# picr22-team-snax-mainboard.net
KiCad netlist of a schematic drawn in Altium Designer
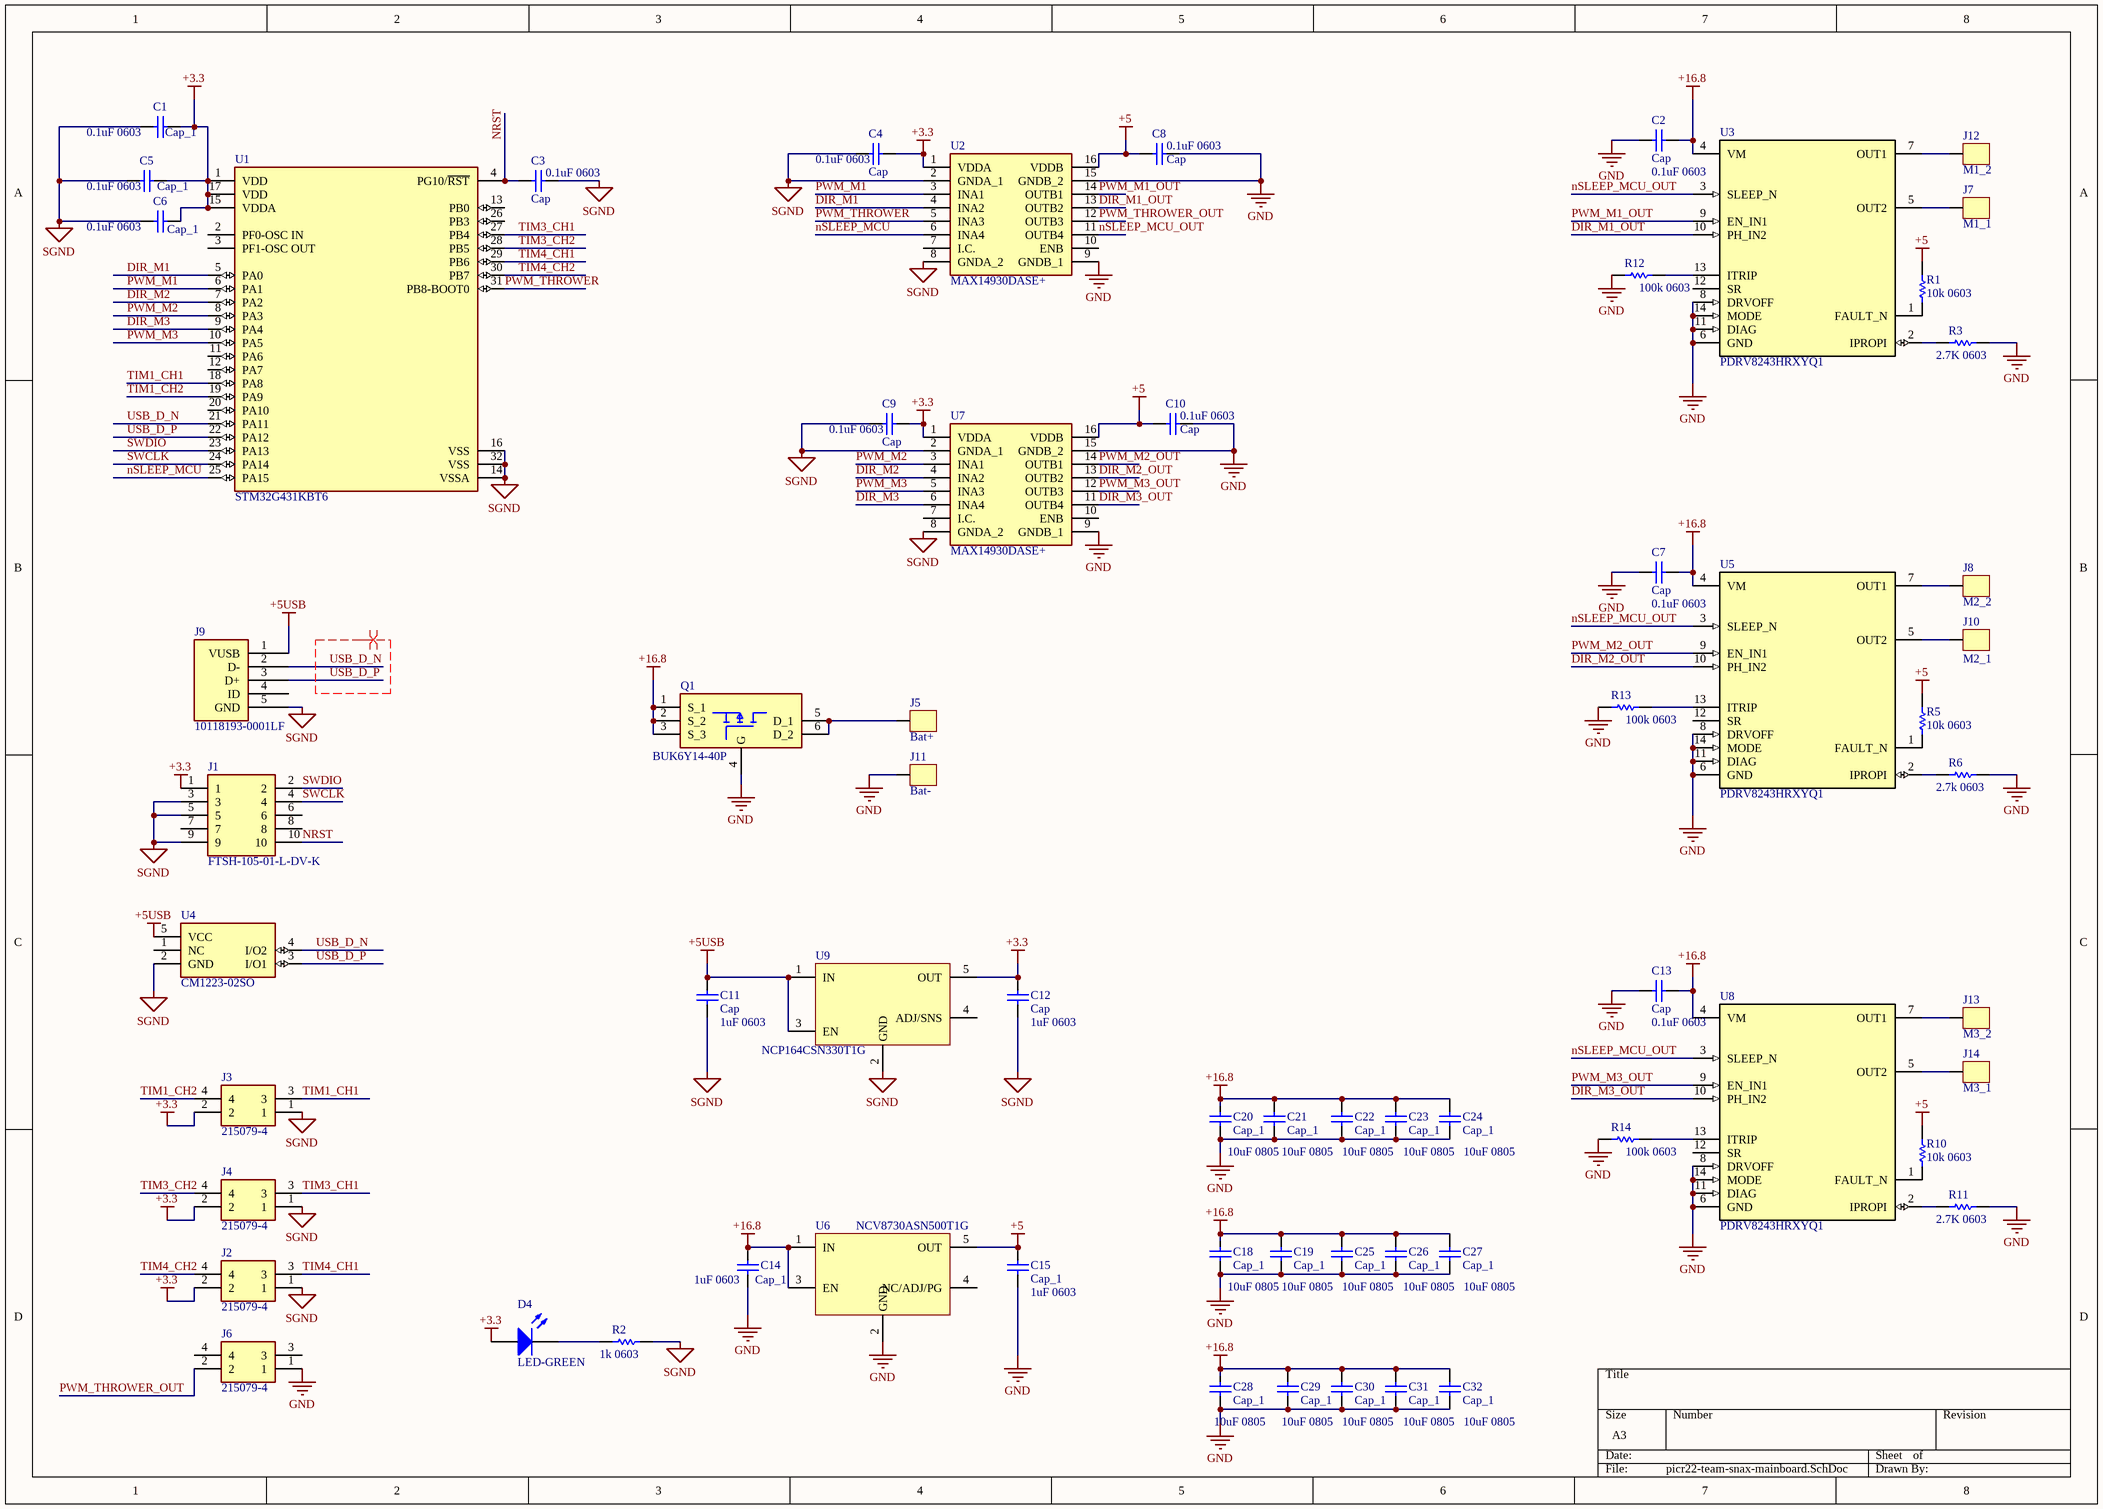
[diagram p0: picr22-team-snax-mainboard.SchDoc]

(export (version "E")
  (design (tool "Eeschema 10.0.6"))
  (components
    (comp (ref "C1")
      (value "Cap_1")
      (footprint "Cap_0603")
      (description "Capacitor")
      (fields (field (name "ALTIUM_VALUE") "0.1uF 0603") (field (name "PUBLISHER") "Altium Limited"))
      (libsource (lib "") (part "Cap_1"))
    )
    (comp (ref "C2")
      (value "Cap")
      (footprint "Cap_0603")
      (description "Capacitor")
      (fields (field (name "ALTIUM_VALUE") "0.1uF 0603") (field (name "PUBLISHER") "Altium Limited"))
      (libsource (lib "MotorDriver") (part "Cap"))
    )
    (comp (ref "C3")
      (value "Cap")
      (footprint "Cap_0603")
      (description "Capacitor")
      (fields (field (name "ALTIUM_VALUE") "0.1uF 0603") (field (name "PUBLISHER") "Altium Limited"))
      (libsource (lib "MotorDriver") (part "Cap"))
    )
    (comp (ref "C4")
      (value "Cap")
      (footprint "Cap_0603")
      (description "Capacitor")
      (fields (field (name "ALTIUM_VALUE") "0.1uF 0603") (field (name "PUBLISHER") "Altium Limited"))
      (libsource (lib "MotorDriver") (part "Cap"))
    )
    (comp (ref "C5")
      (value "Cap_1")
      (footprint "Cap_0603")
      (description "Capacitor")
      (fields (field (name "ALTIUM_VALUE") "0.1uF 0603") (field (name "PUBLISHER") "Altium Limited"))
      (libsource (lib "") (part "Cap_1"))
    )
    (comp (ref "C6")
      (value "Cap_1")
      (footprint "Cap_0603")
      (description "Capacitor")
      (fields (field (name "ALTIUM_VALUE") "0.1uF 0603") (field (name "PUBLISHER") "Altium Limited"))
      (libsource (lib "") (part "Cap_1"))
    )
    (comp (ref "C7")
      (value "Cap")
      (footprint "Cap_0603")
      (description "Capacitor")
      (fields (field (name "ALTIUM_VALUE") "0.1uF 0603") (field (name "PUBLISHER") "Altium Limited"))
      (libsource (lib "MotorDriver") (part "Cap"))
    )
    (comp (ref "C8")
      (value "Cap")
      (footprint "Cap_0603")
      (description "Capacitor")
      (fields (field (name "ALTIUM_VALUE") "0.1uF 0603") (field (name "PUBLISHER") "Altium Limited"))
      (libsource (lib "MotorDriver") (part "Cap"))
    )
    (comp (ref "C9")
      (value "Cap")
      (footprint "Cap_0603")
      (description "Capacitor")
      (fields (field (name "ALTIUM_VALUE") "0.1uF 0603") (field (name "PUBLISHER") "Altium Limited"))
      (libsource (lib "MotorDriver") (part "Cap"))
    )
    (comp (ref "C10")
      (value "Cap")
      (footprint "Cap_0603")
      (description "Capacitor")
      (fields (field (name "ALTIUM_VALUE") "0.1uF 0603") (field (name "PUBLISHER") "Altium Limited"))
      (libsource (lib "MotorDriver") (part "Cap"))
    )
    (comp (ref "C11")
      (value "Cap")
      (footprint "Cap_0603")
      (description "Capacitor")
      (fields (field (name "ALTIUM_VALUE") "1uF 0603") (field (name "PUBLISHER") "Altium Limited"))
      (libsource (lib "MotorDriver") (part "Cap"))
    )
    (comp (ref "C12")
      (value "Cap")
      (footprint "Cap_0603")
      (description "Capacitor")
      (fields (field (name "ALTIUM_VALUE") "1uF 0603") (field (name "PUBLISHER") "Altium Limited"))
      (libsource (lib "MotorDriver") (part "Cap"))
    )
    (comp (ref "C13")
      (value "Cap")
      (footprint "Cap_0603")
      (description "Capacitor")
      (fields (field (name "ALTIUM_VALUE") "0.1uF 0603") (field (name "PUBLISHER") "Altium Limited"))
      (libsource (lib "MotorDriver") (part "Cap"))
    )
    (comp (ref "C14")
      (value "Cap_1")
      (footprint "Cap_0603")
      (description "Capacitor")
      (fields (field (name "ALTIUM_VALUE") "1uF 0603") (field (name "PUBLISHER") "Altium Limited"))
      (libsource (lib "MotorDriver") (part "Cap"))
    )
    (comp (ref "C15")
      (value "Cap_1")
      (footprint "Cap_0603")
      (description "Capacitor")
      (fields (field (name "ALTIUM_VALUE") "1uF 0603") (field (name "PUBLISHER") "Altium Limited"))
      (libsource (lib "MotorDriver") (part "Cap"))
    )
    (comp (ref "C18")
      (value "Cap_1")
      (footprint "CAP_0805")
      (description "Capacitor")
      (fields (field (name "ALTIUM_VALUE") "10uF 0805") (field (name "PUBLISHER") "Altium Limited"))
      (libsource (lib "MotorDriver") (part "Cap_1"))
    )
    (comp (ref "C19")
      (value "Cap_1")
      (footprint "CAP_0805")
      (description "Capacitor")
      (fields (field (name "ALTIUM_VALUE") "10uF 0805") (field (name "PUBLISHER") "Altium Limited"))
      (libsource (lib "MotorDriver") (part "Cap_1"))
    )
    (comp (ref "C20")
      (value "Cap_1")
      (footprint "CAP_0805")
      (description "Capacitor")
      (fields (field (name "ALTIUM_VALUE") "10uF 0805") (field (name "PUBLISHER") "Altium Limited"))
      (libsource (lib "MotorDriver") (part "Cap_1"))
    )
    (comp (ref "C21")
      (value "Cap_1")
      (footprint "CAP_0805")
      (description "Capacitor")
      (fields (field (name "ALTIUM_VALUE") "10uF 0805") (field (name "PUBLISHER") "Altium Limited"))
      (libsource (lib "MotorDriver") (part "Cap_1"))
    )
    (comp (ref "C22")
      (value "Cap_1")
      (footprint "CAP_0805")
      (description "Capacitor")
      (fields (field (name "ALTIUM_VALUE") "10uF 0805") (field (name "PUBLISHER") "Altium Limited"))
      (libsource (lib "MotorDriver") (part "Cap_1"))
    )
    (comp (ref "C23")
      (value "Cap_1")
      (footprint "CAP_0805")
      (description "Capacitor")
      (fields (field (name "ALTIUM_VALUE") "10uF 0805") (field (name "PUBLISHER") "Altium Limited"))
      (libsource (lib "MotorDriver") (part "Cap_1"))
    )
    (comp (ref "C24")
      (value "Cap_1")
      (footprint "CAP_0805")
      (description "Capacitor")
      (fields (field (name "ALTIUM_VALUE") "10uF 0805") (field (name "PUBLISHER") "Altium Limited"))
      (libsource (lib "MotorDriver") (part "Cap_1"))
    )
    (comp (ref "C25")
      (value "Cap_1")
      (footprint "CAP_0805")
      (description "Capacitor")
      (fields (field (name "ALTIUM_VALUE") "10uF 0805") (field (name "PUBLISHER") "Altium Limited"))
      (libsource (lib "MotorDriver") (part "Cap_1"))
    )
    (comp (ref "C26")
      (value "Cap_1")
      (footprint "CAP_0805")
      (description "Capacitor")
      (fields (field (name "ALTIUM_VALUE") "10uF 0805") (field (name "PUBLISHER") "Altium Limited"))
      (libsource (lib "MotorDriver") (part "Cap_1"))
    )
    (comp (ref "C27")
      (value "Cap_1")
      (footprint "CAP_0805")
      (description "Capacitor")
      (fields (field (name "ALTIUM_VALUE") "10uF 0805") (field (name "PUBLISHER") "Altium Limited"))
      (libsource (lib "MotorDriver") (part "Cap_1"))
    )
    (comp (ref "C28")
      (value "Cap_1")
      (footprint "CAP_0805")
      (description "Capacitor")
      (fields (field (name "ALTIUM_VALUE") "10uF 0805") (field (name "PUBLISHER") "Altium Limited"))
      (libsource (lib "MotorDriver") (part "Cap_1"))
    )
    (comp (ref "C29")
      (value "Cap_1")
      (footprint "CAP_0805")
      (description "Capacitor")
      (fields (field (name "ALTIUM_VALUE") "10uF 0805") (field (name "PUBLISHER") "Altium Limited"))
      (libsource (lib "MotorDriver") (part "Cap_1"))
    )
    (comp (ref "C30")
      (value "Cap_1")
      (footprint "CAP_0805")
      (description "Capacitor")
      (fields (field (name "ALTIUM_VALUE") "10uF 0805") (field (name "PUBLISHER") "Altium Limited"))
      (libsource (lib "MotorDriver") (part "Cap_1"))
    )
    (comp (ref "C31")
      (value "Cap_1")
      (footprint "CAP_0805")
      (description "Capacitor")
      (fields (field (name "ALTIUM_VALUE") "10uF 0805") (field (name "PUBLISHER") "Altium Limited"))
      (libsource (lib "MotorDriver") (part "Cap_1"))
    )
    (comp (ref "C32")
      (value "Cap_1")
      (footprint "CAP_0805")
      (description "Capacitor")
      (fields (field (name "ALTIUM_VALUE") "10uF 0805") (field (name "PUBLISHER") "Altium Limited"))
      (libsource (lib "MotorDriver") (part "Cap_1"))
    )
    (comp (ref "D4")
      (value "LED-GREEN")
      (footprint "LED0805G")
      (description "GREEN  LED,Case 0805")
      (libsource (lib "MotorDriver") (part "SMD 0805 LED-GREEN"))
    )
    (comp (ref "J1")
      (value "FTSH-105-01-L-DV-K")
      (footprint "FTSH10501LDVK")
      (description "Connector")
      (fields (field (name "MOUSER PART NUMBER") "200-FTSH10501LDVK"))
      (libsource (lib "MotorDriver") (part "FTSH-105-01-L-DV-K"))
    )
    (comp (ref "J2")
      (value "215079-4")
      (footprint "2150794")
      (description "Connector")
      (fields (field (name "MOUSER PART NUMBER") "571-215079-4"))
      (libsource (lib "MotorDriver") (part "215079-4"))
    )
    (comp (ref "J3")
      (value "215079-4")
      (footprint "2150794")
      (description "Connector")
      (fields (field (name "MOUSER PART NUMBER") "571-215079-4"))
      (libsource (lib "MotorDriver") (part "215079-4"))
    )
    (comp (ref "J4")
      (value "215079-4")
      (footprint "2150794")
      (description "Connector")
      (fields (field (name "MOUSER PART NUMBER") "571-215079-4"))
      (libsource (lib "MotorDriver") (part "215079-4"))
    )
    (comp (ref "J5")
      (value "Bat+")
      (footprint "3x3mm pad")
      (libsource (lib "picr22-snax-mainboard-lib") (part "Connector pad"))
    )
    (comp (ref "J6")
      (value "215079-4")
      (footprint "2150794")
      (description "Connector")
      (fields (field (name "MOUSER PART NUMBER") "571-215079-4"))
      (libsource (lib "MotorDriver") (part "215079-4"))
    )
    (comp (ref "J7")
      (value "M1_1")
      (footprint "3x3mm pad")
      (libsource (lib "picr22-snax-mainboard-lib") (part "Connector pad"))
    )
    (comp (ref "J8")
      (value "M2_2")
      (footprint "3x3mm pad")
      (libsource (lib "picr22-snax-mainboard-lib") (part "Connector pad"))
    )
    (comp (ref "J9")
      (value "10118193-0001LF")
      (footprint "USB port")
      (description "USB - micro B USB 2.0 Receptacle Connector 5 Position Surface Mount, Right Angle; Through Hole")
      (fields (field (name "MF") "Amphenol ICC"))
      (libsource (lib "picr22-snax-mainboard-lib") (part "10118193-0001LF"))
    )
    (comp (ref "J10")
      (value "M2_1")
      (footprint "3x3mm pad")
      (libsource (lib "picr22-snax-mainboard-lib") (part "Connector pad"))
    )
    (comp (ref "J11")
      (value "Bat-")
      (footprint "3x3mm pad")
      (libsource (lib "picr22-snax-mainboard-lib") (part "Connector pad"))
    )
    (comp (ref "J12")
      (value "M1_2")
      (footprint "3x3mm pad")
      (libsource (lib "picr22-snax-mainboard-lib") (part "Connector pad"))
    )
    (comp (ref "J13")
      (value "M3_2")
      (footprint "3x3mm pad")
      (libsource (lib "picr22-snax-mainboard-lib") (part "Connector pad"))
    )
    (comp (ref "J14")
      (value "M3_1")
      (footprint "3x3mm pad")
      (libsource (lib "picr22-snax-mainboard-lib") (part "Connector pad"))
    )
    (comp (ref "Q1")
      (value "BUK6Y14-40P")
      (footprint "SamacSys:BUK6Y1440PX")
      (description "MOSFET (P-Channel)")
      (fields
        (field (name "MANUFACTURER_PART_NUMBER") "BUK6Y14-40PX")
        (field (name "MOUSER PART NUMBER") "771-BUK6Y14-40PX")
      )
      (libsource (lib "MotorDriver") (part "BUK6Y14-40PX"))
    )
    (comp (ref "R1")
      (value "10k 0603")
      (footprint "RES_0603")
      (description "Resistor")
      (fields (field (name "PUBLISHER") "Altium Limited"))
      (libsource (lib "MotorDriver") (part "Res1"))
    )
    (comp (ref "R2")
      (value "1k 0603")
      (footprint "RES_0603")
      (description "Resistor")
      (fields (field (name "PUBLISHER") "Altium Limited"))
      (libsource (lib "MotorDriver") (part "Res1"))
    )
    (comp (ref "R3")
      (value "2.7K 0603")
      (footprint "RES_0603")
      (description "Resistor")
      (fields (field (name "PUBLISHER") "Altium Limited"))
      (libsource (lib "MotorDriver") (part "Res1"))
    )
    (comp (ref "R5")
      (value "10k 0603")
      (footprint "RES_0603")
      (description "Resistor")
      (fields (field (name "PUBLISHER") "Altium Limited"))
      (libsource (lib "MotorDriver") (part "Res1"))
    )
    (comp (ref "R6")
      (value "2.7k 0603")
      (footprint "RES_0603")
      (description "Resistor")
      (fields (field (name "PUBLISHER") "Altium Limited"))
      (libsource (lib "MotorDriver") (part "Res1"))
    )
    (comp (ref "R10")
      (value "10k 0603")
      (footprint "RES_0603")
      (description "Resistor")
      (fields (field (name "PUBLISHER") "Altium Limited"))
      (libsource (lib "MotorDriver") (part "Res1"))
    )
    (comp (ref "R11")
      (value "2.7K 0603")
      (footprint "RES_0603")
      (description "Resistor")
      (fields (field (name "PUBLISHER") "Altium Limited"))
      (libsource (lib "MotorDriver") (part "Res1"))
    )
    (comp (ref "R12")
      (value "100k 0603")
      (footprint "RES_0603")
      (description "Resistor")
      (fields (field (name "PUBLISHER") "Altium Limited"))
      (libsource (lib "MotorDriver") (part "Res1"))
    )
    (comp (ref "R13")
      (value "100k 0603")
      (footprint "RES_0603")
      (description "Resistor")
      (fields (field (name "PUBLISHER") "Altium Limited"))
      (libsource (lib "MotorDriver") (part "Res1"))
    )
    (comp (ref "R14")
      (value "100k 0603")
      (footprint "RES_0603")
      (description "Resistor")
      (fields (field (name "PUBLISHER") "Altium Limited"))
      (libsource (lib "MotorDriver") (part "Res1"))
    )
    (comp (ref "U1")
      (value "STM32G431KBT6")
      (footprint "FP-LQFP32-5V-IPC_B")
      (description "IC MCU 32BIT 128KB FLASH 32LQFP")
      (libsource (lib "Altium Content Vault") (part "c9e0a49b9ddd2147befd892ac7d673c"))
    )
    (comp (ref "U2")
      (value "MAX14930DASE+")
      (footprint "SOIC127P1032X265-16N")
      (description "Integrated Circuit")
      (fields
        (field (name "MANUFACTURER_PART_NUMBER") "MAX14930DAWE+")
        (field (name "MOUSER PART NUMBER") "700-MAX14930DAWE+")
      )
      (libsource (lib "MotorDriver") (part "MAX14930DAWE+"))
    )
    (comp (ref "U3")
      (value "PDRV8243HRXYQ1")
      (footprint "RXY0014A-MFG")
      (description "No Description Available")
      (fields (field (name "COPYRIGHT") "Copyright (C) 2022 Ultra Librarian. All rights reserved."))
      (libsource (lib "picr22-snax-mainboard-lib") (part "PDRV8243HRXYQ1"))
    )
    (comp (ref "U4")
      (value "CM1223-02SO")
      (footprint "SOT23-5")
      (description "Integrated Circuit")
      (fields
        (field (name "MANUFACTURER_PART_NUMBER") "SP3003-02JTG")
        (field (name "MOUSER PART NUMBER") "576-SP3003-02JTG")
      )
      (libsource (lib "MotorDriver") (part "SP3003-02JTG"))
    )
    (comp (ref "U5")
      (value "PDRV8243HRXYQ1")
      (footprint "RXY0014A-MFG")
      (description "No Description Available")
      (fields (field (name "COPYRIGHT") "Copyright (C) 2022 Ultra Librarian. All rights reserved."))
      (libsource (lib "picr22-snax-mainboard-lib") (part "PDRV8243HRXYQ1"))
    )
    (comp (ref "U6")
      (value "NCV8730ASN500T1G")
      (footprint "SOT23-5")
      (libsource (lib "MotorDriver") (part "NCV8730ASN500T1G"))
    )
    (comp (ref "U7")
      (value "MAX14930DASE+")
      (footprint "SOIC127P1032X265-16N")
      (description "Integrated Circuit")
      (fields
        (field (name "MANUFACTURER_PART_NUMBER") "MAX14930DAWE+")
        (field (name "MOUSER PART NUMBER") "700-MAX14930DAWE+")
      )
      (libsource (lib "MotorDriver") (part "MAX14930DAWE+"))
    )
    (comp (ref "U8")
      (value "PDRV8243HRXYQ1")
      (footprint "RXY0014A-MFG")
      (description "No Description Available")
      (fields (field (name "COPYRIGHT") "Copyright (C) 2022 Ultra Librarian. All rights reserved."))
      (libsource (lib "picr22-snax-mainboard-lib") (part "PDRV8243HRXYQ1"))
    )
    (comp (ref "U9")
      (value "NCP164CSN330T1G")
      (footprint "SOT23-5")
      (libsource (lib "MotorDriver") (part "NCV8730ASN500T1G_1"))
    )
  )
  (nets
    (net (code "1") (name "+3.3") (class "Default")
      (node (ref "C1") (pin "2") (pinfunction "2_2") (pintype "passive"))
      (node (ref "C12") (pin "2") (pinfunction "2_2") (pintype "passive"))
      (node (ref "C4") (pin "1") (pinfunction "1_1") (pintype "passive"))
      (node (ref "C5") (pin "2") (pinfunction "2_2") (pintype "passive"))
      (node (ref "C6") (pin "2") (pinfunction "2_2") (pintype "passive"))
      (node (ref "C9") (pin "1") (pinfunction "1_1") (pintype "passive"))
      (node (ref "D4") (pin "A") (pinfunction "A_A") (pintype "passive"))
      (node (ref "J1") (pin "1") (pinfunction "1_1") (pintype "passive"))
      (node (ref "J2") (pin "2") (pinfunction "2_2") (pintype "passive"))
      (node (ref "J3") (pin "2") (pinfunction "2_2") (pintype "passive"))
      (node (ref "J4") (pin "2") (pinfunction "2_2") (pintype "passive"))
      (node (ref "U1") (pin "1") (pinfunction "VDD_1") (pintype "power_in"))
      (node (ref "U1") (pin "15") (pinfunction "VDDA_15") (pintype "power_in"))
      (node (ref "U1") (pin "17") (pinfunction "VDD_17") (pintype "power_in"))
      (node (ref "U2") (pin "1") (pinfunction "VDDA_1") (pintype "passive"))
      (node (ref "U7") (pin "1") (pinfunction "VDDA_1") (pintype "passive"))
      (node (ref "U9") (pin "5") (pinfunction "OUT_5") (pintype "passive"))
    )
    (net (code "2") (name "+5") (class "Default")
      (node (ref "C10") (pin "2") (pinfunction "2_2") (pintype "passive"))
      (node (ref "C15") (pin "2") (pinfunction "2_2") (pintype "passive"))
      (node (ref "C8") (pin "2") (pinfunction "2_2") (pintype "passive"))
      (node (ref "R1") (pin "2") (pinfunction "2_2") (pintype "passive"))
      (node (ref "R10") (pin "2") (pinfunction "2_2") (pintype "passive"))
      (node (ref "R5") (pin "2") (pinfunction "2_2") (pintype "passive"))
      (node (ref "U2") (pin "16") (pinfunction "VDDB_16") (pintype "passive"))
      (node (ref "U6") (pin "5") (pinfunction "OUT_5") (pintype "passive"))
      (node (ref "U7") (pin "16") (pinfunction "VDDB_16") (pintype "passive"))
    )
    (net (code "3") (name "+5USB") (class "Default")
      (node (ref "C11") (pin "2") (pinfunction "2_2") (pintype "passive"))
      (node (ref "J9") (pin "1") (pinfunction "VUSB_1") (pintype "power_in"))
      (node (ref "U4") (pin "5") (pinfunction "VCC_5") (pintype "power_in"))
      (node (ref "U9") (pin "1") (pinfunction "IN_1") (pintype "passive"))
      (node (ref "U9") (pin "3") (pinfunction "EN_3") (pintype "passive"))
    )
    (net (code "4") (name "+16.8") (class "Default")
      (node (ref "C13") (pin "2") (pinfunction "2_2") (pintype "passive"))
      (node (ref "C14") (pin "2") (pinfunction "2_2") (pintype "passive"))
      (node (ref "C18") (pin "2") (pinfunction "2_2") (pintype "passive"))
      (node (ref "C19") (pin "2") (pinfunction "2_2") (pintype "passive"))
      (node (ref "C2") (pin "2") (pinfunction "2_2") (pintype "passive"))
      (node (ref "C20") (pin "2") (pinfunction "2_2") (pintype "passive"))
      (node (ref "C21") (pin "2") (pinfunction "2_2") (pintype "passive"))
      (node (ref "C22") (pin "2") (pinfunction "2_2") (pintype "passive"))
      (node (ref "C23") (pin "2") (pinfunction "2_2") (pintype "passive"))
      (node (ref "C24") (pin "2") (pinfunction "2_2") (pintype "passive"))
      (node (ref "C25") (pin "2") (pinfunction "2_2") (pintype "passive"))
      (node (ref "C26") (pin "2") (pinfunction "2_2") (pintype "passive"))
      (node (ref "C27") (pin "2") (pinfunction "2_2") (pintype "passive"))
      (node (ref "C28") (pin "2") (pinfunction "2_2") (pintype "passive"))
      (node (ref "C29") (pin "2") (pinfunction "2_2") (pintype "passive"))
      (node (ref "C30") (pin "2") (pinfunction "2_2") (pintype "passive"))
      (node (ref "C31") (pin "2") (pinfunction "2_2") (pintype "passive"))
      (node (ref "C32") (pin "2") (pinfunction "2_2") (pintype "passive"))
      (node (ref "C7") (pin "2") (pinfunction "2_2") (pintype "passive"))
      (node (ref "Q1") (pin "1") (pinfunction "S_1_1") (pintype "passive"))
      (node (ref "Q1") (pin "2") (pinfunction "S_2_2") (pintype "passive"))
      (node (ref "Q1") (pin "3") (pinfunction "S_3_3") (pintype "passive"))
      (node (ref "U3") (pin "4") (pinfunction "VM_4") (pintype "power_in"))
      (node (ref "U5") (pin "4") (pinfunction "VM_4") (pintype "power_in"))
      (node (ref "U6") (pin "1") (pinfunction "IN_1") (pintype "passive"))
      (node (ref "U6") (pin "3") (pinfunction "EN_3") (pintype "passive"))
      (node (ref "U8") (pin "4") (pinfunction "VM_4") (pintype "power_in"))
    )
    (net (code "5") (name "/DIR_M1") (class "Default")
      (node (ref "U1") (pin "5") (pinfunction "PA0_5") (pintype "bidirectional"))
      (node (ref "U2") (pin "4") (pinfunction "INA2_4") (pintype "passive"))
    )
    (net (code "6") (name "/DIR_M1_OUT") (class "Default")
      (node (ref "U2") (pin "13") (pinfunction "OUTB2_13") (pintype "passive"))
      (node (ref "U3") (pin "10") (pinfunction "PH_IN2_10") (pintype "input"))
    )
    (net (code "7") (name "/DIR_M2") (class "Default")
      (node (ref "U1") (pin "7") (pinfunction "PA2_7") (pintype "bidirectional"))
      (node (ref "U7") (pin "4") (pinfunction "INA2_4") (pintype "passive"))
    )
    (net (code "8") (name "/DIR_M2_OUT") (class "Default")
      (node (ref "U5") (pin "10") (pinfunction "PH_IN2_10") (pintype "input"))
      (node (ref "U7") (pin "13") (pinfunction "OUTB2_13") (pintype "passive"))
    )
    (net (code "9") (name "/DIR_M3") (class "Default")
      (node (ref "U1") (pin "9") (pinfunction "PA4_9") (pintype "bidirectional"))
      (node (ref "U7") (pin "6") (pinfunction "INA4_6") (pintype "passive"))
    )
    (net (code "10") (name "/DIR_M3_OUT") (class "Default")
      (node (ref "U7") (pin "11") (pinfunction "OUTB4_11") (pintype "passive"))
      (node (ref "U8") (pin "10") (pinfunction "PH_IN2_10") (pintype "input"))
    )
    (net (code "11") (name "/NRST") (class "Default")
      (node (ref "C3") (pin "2") (pinfunction "2_2") (pintype "passive"))
      (node (ref "J1") (pin "10") (pinfunction "10_10") (pintype "passive"))
      (node (ref "U1") (pin "4") (pinfunction "PG10/~{RST}_4") (pintype "passive"))
    )
    (net (code "12") (name "/PWM_M1") (class "Default")
      (node (ref "U1") (pin "6") (pinfunction "PA1_6") (pintype "bidirectional"))
      (node (ref "U2") (pin "3") (pinfunction "INA1_3") (pintype "passive"))
    )
    (net (code "13") (name "/PWM_M1_OUT") (class "Default")
      (node (ref "U2") (pin "14") (pinfunction "OUTB1_14") (pintype "passive"))
      (node (ref "U3") (pin "9") (pinfunction "EN_IN1_9") (pintype "input"))
    )
    (net (code "14") (name "/PWM_M2") (class "Default")
      (node (ref "U1") (pin "8") (pinfunction "PA3_8") (pintype "bidirectional"))
      (node (ref "U7") (pin "3") (pinfunction "INA1_3") (pintype "passive"))
    )
    (net (code "15") (name "/PWM_M2_OUT") (class "Default")
      (node (ref "U5") (pin "9") (pinfunction "EN_IN1_9") (pintype "input"))
      (node (ref "U7") (pin "14") (pinfunction "OUTB1_14") (pintype "passive"))
    )
    (net (code "16") (name "/PWM_M3") (class "Default")
      (node (ref "U1") (pin "10") (pinfunction "PA5_10") (pintype "bidirectional"))
      (node (ref "U7") (pin "5") (pinfunction "INA3_5") (pintype "passive"))
    )
    (net (code "17") (name "/PWM_M3_OUT") (class "Default")
      (node (ref "U7") (pin "12") (pinfunction "OUTB3_12") (pintype "passive"))
      (node (ref "U8") (pin "9") (pinfunction "EN_IN1_9") (pintype "input"))
    )
    (net (code "18") (name "/PWM_THROWER") (class "Default")
      (node (ref "U1") (pin "31") (pinfunction "PB8-BOOT0_31") (pintype "bidirectional"))
      (node (ref "U2") (pin "5") (pinfunction "INA3_5") (pintype "passive"))
    )
    (net (code "19") (name "/PWM_THROWER_OUT") (class "Default")
      (node (ref "J6") (pin "2") (pinfunction "2_2") (pintype "passive"))
      (node (ref "U2") (pin "12") (pinfunction "OUTB3_12") (pintype "passive"))
    )
    (net (code "20") (name "/SWCLK") (class "Default")
      (node (ref "J1") (pin "4") (pinfunction "4_4") (pintype "passive"))
      (node (ref "U1") (pin "24") (pinfunction "PA14_24") (pintype "bidirectional"))
    )
    (net (code "21") (name "/SWDIO") (class "Default")
      (node (ref "J1") (pin "2") (pinfunction "2_2") (pintype "passive"))
      (node (ref "U1") (pin "23") (pinfunction "PA13_23") (pintype "bidirectional"))
    )
    (net (code "22") (name "/TIM1_CH1") (class "Default")
      (node (ref "J3") (pin "3") (pinfunction "3_3") (pintype "passive"))
      (node (ref "U1") (pin "18") (pinfunction "PA8_18") (pintype "bidirectional"))
    )
    (net (code "23") (name "/TIM1_CH2") (class "Default")
      (node (ref "J3") (pin "4") (pinfunction "4_4") (pintype "passive"))
      (node (ref "U1") (pin "19") (pinfunction "PA9_19") (pintype "bidirectional"))
    )
    (net (code "24") (name "/TIM3_CH1") (class "Default")
      (node (ref "J4") (pin "3") (pinfunction "3_3") (pintype "passive"))
      (node (ref "U1") (pin "27") (pinfunction "PB4_27") (pintype "bidirectional"))
    )
    (net (code "25") (name "/TIM3_CH2") (class "Default")
      (node (ref "J4") (pin "4") (pinfunction "4_4") (pintype "passive"))
      (node (ref "U1") (pin "28") (pinfunction "PB5_28") (pintype "bidirectional"))
    )
    (net (code "26") (name "/TIM4_CH1") (class "Default")
      (node (ref "J2") (pin "3") (pinfunction "3_3") (pintype "passive"))
      (node (ref "U1") (pin "29") (pinfunction "PB6_29") (pintype "bidirectional"))
    )
    (net (code "27") (name "/TIM4_CH2") (class "Default")
      (node (ref "J2") (pin "4") (pinfunction "4_4") (pintype "passive"))
      (node (ref "U1") (pin "30") (pinfunction "PB7_30") (pintype "bidirectional"))
    )
    (net (code "28") (name "/USB_D_N") (class "Default")
      (node (ref "J9") (pin "2") (pinfunction "D-_2") (pintype "passive"))
      (node (ref "U1") (pin "21") (pinfunction "PA11_21") (pintype "bidirectional"))
      (node (ref "U4") (pin "4") (pinfunction "I/O2_4") (pintype "bidirectional"))
    )
    (net (code "29") (name "/USB_D_P") (class "Default")
      (node (ref "J9") (pin "3") (pinfunction "D+_3") (pintype "passive"))
      (node (ref "U1") (pin "22") (pinfunction "PA12_22") (pintype "bidirectional"))
      (node (ref "U4") (pin "3") (pinfunction "I/O1_3") (pintype "bidirectional"))
    )
    (net (code "30") (name "/nSLEEP_MCU") (class "Default")
      (node (ref "U1") (pin "25") (pinfunction "PA15_25") (pintype "bidirectional"))
      (node (ref "U2") (pin "6") (pinfunction "INA4_6") (pintype "passive"))
    )
    (net (code "31") (name "/nSLEEP_MCU_OUT") (class "Default")
      (node (ref "U2") (pin "11") (pinfunction "OUTB4_11") (pintype "passive"))
      (node (ref "U3") (pin "3") (pinfunction "SLEEP_N_3") (pintype "input"))
      (node (ref "U5") (pin "3") (pinfunction "SLEEP_N_3") (pintype "input"))
      (node (ref "U8") (pin "3") (pinfunction "SLEEP_N_3") (pintype "input"))
    )
    (net (code "32") (name "GND") (class "Default")
      (node (ref "C10") (pin "1") (pinfunction "1_1") (pintype "passive"))
      (node (ref "C13") (pin "1") (pinfunction "1_1") (pintype "passive"))
      (node (ref "C14") (pin "1") (pinfunction "1_1") (pintype "passive"))
      (node (ref "C15") (pin "1") (pinfunction "1_1") (pintype "passive"))
      (node (ref "C18") (pin "1") (pinfunction "1_1") (pintype "passive"))
      (node (ref "C19") (pin "1") (pinfunction "1_1") (pintype "passive"))
      (node (ref "C2") (pin "1") (pinfunction "1_1") (pintype "passive"))
      (node (ref "C20") (pin "1") (pinfunction "1_1") (pintype "passive"))
      (node (ref "C21") (pin "1") (pinfunction "1_1") (pintype "passive"))
      (node (ref "C22") (pin "1") (pinfunction "1_1") (pintype "passive"))
      (node (ref "C23") (pin "1") (pinfunction "1_1") (pintype "passive"))
      (node (ref "C24") (pin "1") (pinfunction "1_1") (pintype "passive"))
      (node (ref "C25") (pin "1") (pinfunction "1_1") (pintype "passive"))
      (node (ref "C26") (pin "1") (pinfunction "1_1") (pintype "passive"))
      (node (ref "C27") (pin "1") (pinfunction "1_1") (pintype "passive"))
      (node (ref "C28") (pin "1") (pinfunction "1_1") (pintype "passive"))
      (node (ref "C29") (pin "1") (pinfunction "1_1") (pintype "passive"))
      (node (ref "C30") (pin "1") (pinfunction "1_1") (pintype "passive"))
      (node (ref "C31") (pin "1") (pinfunction "1_1") (pintype "passive"))
      (node (ref "C32") (pin "1") (pinfunction "1_1") (pintype "passive"))
      (node (ref "C7") (pin "1") (pinfunction "1_1") (pintype "passive"))
      (node (ref "C8") (pin "1") (pinfunction "1_1") (pintype "passive"))
      (node (ref "J11") (pin "1") (pinfunction "6_1") (pintype "passive"))
      (node (ref "J6") (pin "1") (pinfunction "1_1") (pintype "passive"))
      (node (ref "Q1") (pin "4") (pinfunction "G_4") (pintype "passive"))
      (node (ref "R11") (pin "2") (pinfunction "2_2") (pintype "passive"))
      (node (ref "R12") (pin "1") (pinfunction "1_1") (pintype "passive"))
      (node (ref "R13") (pin "1") (pinfunction "1_1") (pintype "passive"))
      (node (ref "R14") (pin "1") (pinfunction "1_1") (pintype "passive"))
      (node (ref "R3") (pin "2") (pinfunction "2_2") (pintype "passive"))
      (node (ref "R6") (pin "2") (pinfunction "2_2") (pintype "passive"))
      (node (ref "U2") (pin "15") (pinfunction "GNDB_2_15") (pintype "passive"))
      (node (ref "U2") (pin "9") (pinfunction "GNDB_1_9") (pintype "passive"))
      (node (ref "U3") (pin "11") (pinfunction "DIAG_11") (pintype "input"))
      (node (ref "U3") (pin "14") (pinfunction "MODE_14") (pintype "input"))
      (node (ref "U3") (pin "6") (pinfunction "GND_6") (pintype "power_in"))
      (node (ref "U3") (pin "8") (pinfunction "DRVOFF_8") (pintype "input"))
      (node (ref "U5") (pin "11") (pinfunction "DIAG_11") (pintype "input"))
      (node (ref "U5") (pin "14") (pinfunction "MODE_14") (pintype "input"))
      (node (ref "U5") (pin "6") (pinfunction "GND_6") (pintype "power_in"))
      (node (ref "U5") (pin "8") (pinfunction "DRVOFF_8") (pintype "input"))
      (node (ref "U6") (pin "2") (pinfunction "GND_2") (pintype "passive"))
      (node (ref "U7") (pin "15") (pinfunction "GNDB_2_15") (pintype "passive"))
      (node (ref "U7") (pin "9") (pinfunction "GNDB_1_9") (pintype "passive"))
      (node (ref "U8") (pin "11") (pinfunction "DIAG_11") (pintype "input"))
      (node (ref "U8") (pin "14") (pinfunction "MODE_14") (pintype "input"))
      (node (ref "U8") (pin "6") (pinfunction "GND_6") (pintype "power_in"))
      (node (ref "U8") (pin "8") (pinfunction "DRVOFF_8") (pintype "input"))
    )
    (net (code "33") (name "Net-(D4-PadK)") (class "Default")
      (node (ref "D4") (pin "K") (pinfunction "K_K") (pintype "passive"))
      (node (ref "R2") (pin "1") (pinfunction "1_1") (pintype "passive"))
    )
    (net (code "34") (name "Net-(J5-6)") (class "Default")
      (node (ref "J5") (pin "1") (pinfunction "6_1") (pintype "passive"))
      (node (ref "Q1") (pin "5") (pinfunction "D_1_5") (pintype "passive"))
      (node (ref "Q1") (pin "6") (pinfunction "D_2_6") (pintype "passive"))
    )
    (net (code "35") (name "Net-(J7-6)") (class "Default")
      (node (ref "J7") (pin "1") (pinfunction "6_1") (pintype "passive"))
      (node (ref "U3") (pin "5") (pinfunction "OUT2_5") (pintype "passive"))
    )
    (net (code "36") (name "Net-(J8-6)") (class "Default")
      (node (ref "J8") (pin "1") (pinfunction "6_1") (pintype "passive"))
      (node (ref "U5") (pin "7") (pinfunction "OUT1_7") (pintype "passive"))
    )
    (net (code "37") (name "Net-(J10-6)") (class "Default")
      (node (ref "J10") (pin "1") (pinfunction "6_1") (pintype "passive"))
      (node (ref "U5") (pin "5") (pinfunction "OUT2_5") (pintype "passive"))
    )
    (net (code "38") (name "Net-(J12-6)") (class "Default")
      (node (ref "J12") (pin "1") (pinfunction "6_1") (pintype "passive"))
      (node (ref "U3") (pin "7") (pinfunction "OUT1_7") (pintype "passive"))
    )
    (net (code "39") (name "Net-(J13-6)") (class "Default")
      (node (ref "J13") (pin "1") (pinfunction "6_1") (pintype "passive"))
      (node (ref "U8") (pin "7") (pinfunction "OUT1_7") (pintype "passive"))
    )
    (net (code "40") (name "Net-(J14-6)") (class "Default")
      (node (ref "J14") (pin "1") (pinfunction "6_1") (pintype "passive"))
      (node (ref "U8") (pin "5") (pinfunction "OUT2_5") (pintype "passive"))
    )
    (net (code "41") (name "Net-(U3-FAULT_N)") (class "Default")
      (node (ref "R1") (pin "1") (pinfunction "1_1") (pintype "passive"))
      (node (ref "U3") (pin "1") (pinfunction "FAULT_N_1") (pintype "open_collector"))
    )
    (net (code "42") (name "Net-(U3-IPROPI)") (class "Default")
      (node (ref "R3") (pin "1") (pinfunction "1_1") (pintype "passive"))
      (node (ref "U3") (pin "2") (pinfunction "IPROPI_2") (pintype "bidirectional"))
    )
    (net (code "43") (name "Net-(U3-ITRIP)") (class "Default")
      (node (ref "R12") (pin "2") (pinfunction "2_2") (pintype "passive"))
      (node (ref "U3") (pin "13") (pinfunction "ITRIP_13") (pintype "passive"))
    )
    (net (code "44") (name "Net-(U5-FAULT_N)") (class "Default")
      (node (ref "R5") (pin "1") (pinfunction "1_1") (pintype "passive"))
      (node (ref "U5") (pin "1") (pinfunction "FAULT_N_1") (pintype "open_collector"))
    )
    (net (code "45") (name "Net-(U5-IPROPI)") (class "Default")
      (node (ref "R6") (pin "1") (pinfunction "1_1") (pintype "passive"))
      (node (ref "U5") (pin "2") (pinfunction "IPROPI_2") (pintype "bidirectional"))
    )
    (net (code "46") (name "Net-(U5-ITRIP)") (class "Default")
      (node (ref "R13") (pin "2") (pinfunction "2_2") (pintype "passive"))
      (node (ref "U5") (pin "13") (pinfunction "ITRIP_13") (pintype "passive"))
    )
    (net (code "47") (name "Net-(U8-FAULT_N)") (class "Default")
      (node (ref "R10") (pin "1") (pinfunction "1_1") (pintype "passive"))
      (node (ref "U8") (pin "1") (pinfunction "FAULT_N_1") (pintype "open_collector"))
    )
    (net (code "48") (name "Net-(U8-IPROPI)") (class "Default")
      (node (ref "R11") (pin "1") (pinfunction "1_1") (pintype "passive"))
      (node (ref "U8") (pin "2") (pinfunction "IPROPI_2") (pintype "bidirectional"))
    )
    (net (code "49") (name "Net-(U8-ITRIP)") (class "Default")
      (node (ref "R14") (pin "2") (pinfunction "2_2") (pintype "passive"))
      (node (ref "U8") (pin "13") (pinfunction "ITRIP_13") (pintype "passive"))
    )
    (net (code "50") (name "SGND") (class "Default")
      (node (ref "C1") (pin "1") (pinfunction "1_1") (pintype "passive"))
      (node (ref "C11") (pin "1") (pinfunction "1_1") (pintype "passive"))
      (node (ref "C12") (pin "1") (pinfunction "1_1") (pintype "passive"))
      (node (ref "C3") (pin "1") (pinfunction "1_1") (pintype "passive"))
      (node (ref "C4") (pin "2") (pinfunction "2_2") (pintype "passive"))
      (node (ref "C5") (pin "1") (pinfunction "1_1") (pintype "passive"))
      (node (ref "C6") (pin "1") (pinfunction "1_1") (pintype "passive"))
      (node (ref "C9") (pin "2") (pinfunction "2_2") (pintype "passive"))
      (node (ref "J1") (pin "3") (pinfunction "3_3") (pintype "passive"))
      (node (ref "J1") (pin "5") (pinfunction "5_5") (pintype "passive"))
      (node (ref "J1") (pin "9") (pinfunction "9_9") (pintype "passive"))
      (node (ref "J2") (pin "1") (pinfunction "1_1") (pintype "passive"))
      (node (ref "J3") (pin "1") (pinfunction "1_1") (pintype "passive"))
      (node (ref "J4") (pin "1") (pinfunction "1_1") (pintype "passive"))
      (node (ref "J9") (pin "5") (pinfunction "GND_5") (pintype "power_in"))
      (node (ref "R2") (pin "2") (pinfunction "2_2") (pintype "passive"))
      (node (ref "U1") (pin "14") (pinfunction "VSSA_14") (pintype "power_in"))
      (node (ref "U1") (pin "16") (pinfunction "VSS_16") (pintype "power_in"))
      (node (ref "U1") (pin "32") (pinfunction "VSS_32") (pintype "power_in"))
      (node (ref "U2") (pin "2") (pinfunction "GNDA_1_2") (pintype "passive"))
      (node (ref "U2") (pin "8") (pinfunction "GNDA_2_8") (pintype "passive"))
      (node (ref "U4") (pin "2") (pinfunction "GND_2") (pintype "power_in"))
      (node (ref "U7") (pin "2") (pinfunction "GNDA_1_2") (pintype "passive"))
      (node (ref "U7") (pin "8") (pinfunction "GNDA_2_8") (pintype "passive"))
      (node (ref "U9") (pin "2") (pinfunction "GND_2") (pintype "passive"))
    )
    (net (code "51") (name "unconnected-(J1-Pad6)") (class "Default")
      (node (ref "J1") (pin "6") (pinfunction "6_6") (pintype "passive"))
    )
    (net (code "52") (name "unconnected-(J1-Pad7)") (class "Default")
      (node (ref "J1") (pin "7") (pinfunction "7_7") (pintype "passive"))
    )
    (net (code "53") (name "unconnected-(J1-Pad8)") (class "Default")
      (node (ref "J1") (pin "8") (pinfunction "8_8") (pintype "passive"))
    )
    (net (code "54") (name "unconnected-(J6-Pad3)") (class "Default")
      (node (ref "J6") (pin "3") (pinfunction "3_3") (pintype "passive"))
    )
    (net (code "55") (name "unconnected-(J6-Pad4)") (class "Default")
      (node (ref "J6") (pin "4") (pinfunction "4_4") (pintype "passive"))
    )
    (net (code "56") (name "unconnected-(J9-ID-Pad4)") (class "Default")
      (node (ref "J9") (pin "4") (pinfunction "ID_4") (pintype "passive"))
    )
    (net (code "57") (name "unconnected-(U1-PA6-Pad11)") (class "Default")
      (node (ref "U1") (pin "11") (pinfunction "PA6_11") (pintype "bidirectional"))
    )
    (net (code "58") (name "unconnected-(U1-PA7-Pad12)") (class "Default")
      (node (ref "U1") (pin "12") (pinfunction "PA7_12") (pintype "bidirectional"))
    )
    (net (code "59") (name "unconnected-(U1-PA10-Pad20)") (class "Default")
      (node (ref "U1") (pin "20") (pinfunction "PA10_20") (pintype "bidirectional"))
    )
    (net (code "60") (name "unconnected-(U1-PB0-Pad13)") (class "Default")
      (node (ref "U1") (pin "13") (pinfunction "PB0_13") (pintype "bidirectional"))
    )
    (net (code "61") (name "unconnected-(U1-PB3-Pad26)") (class "Default")
      (node (ref "U1") (pin "26") (pinfunction "PB3_26") (pintype "bidirectional"))
    )
    (net (code "62") (name "unconnected-(U1-PF0-OSC_IN-Pad2)") (class "Default")
      (node (ref "U1") (pin "2") (pinfunction "PF0-OSC_IN_2") (pintype "passive"))
    )
    (net (code "63") (name "unconnected-(U1-PF1-OSC_OUT-Pad3)") (class "Default")
      (node (ref "U1") (pin "3") (pinfunction "PF1-OSC_OUT_3") (pintype "passive"))
    )
    (net (code "64") (name "unconnected-(U2-ENB-Pad10)") (class "Default")
      (node (ref "U2") (pin "10") (pinfunction "ENB_10") (pintype "passive"))
    )
    (net (code "65") (name "unconnected-(U2-I.C.-Pad7)") (class "Default")
      (node (ref "U2") (pin "7") (pinfunction "I.C._7") (pintype "passive"))
    )
    (net (code "66") (name "unconnected-(U3-SR-Pad12)") (class "Default")
      (node (ref "U3") (pin "12") (pinfunction "SR_12") (pintype "passive"))
    )
    (net (code "67") (name "unconnected-(U4-NC-Pad1)") (class "Default")
      (node (ref "U4") (pin "1") (pinfunction "NC_1") (pintype "passive"))
    )
    (net (code "68") (name "unconnected-(U5-SR-Pad12)") (class "Default")
      (node (ref "U5") (pin "12") (pinfunction "SR_12") (pintype "passive"))
    )
    (net (code "69") (name "unconnected-(U6-NC{slash}ADJ{slash}PG-Pad4)") (class "Default")
      (node (ref "U6") (pin "4") (pinfunction "NC/ADJ/PG_4") (pintype "passive"))
    )
    (net (code "70") (name "unconnected-(U7-ENB-Pad10)") (class "Default")
      (node (ref "U7") (pin "10") (pinfunction "ENB_10") (pintype "passive"))
    )
    (net (code "71") (name "unconnected-(U7-I.C.-Pad7)") (class "Default")
      (node (ref "U7") (pin "7") (pinfunction "I.C._7") (pintype "passive"))
    )
    (net (code "72") (name "unconnected-(U8-SR-Pad12)") (class "Default")
      (node (ref "U8") (pin "12") (pinfunction "SR_12") (pintype "passive"))
    )
    (net (code "73") (name "unconnected-(U9-ADJ{slash}SNS-Pad4)") (class "Default")
      (node (ref "U9") (pin "4") (pinfunction "ADJ/SNS_4") (pintype "passive"))
    )
  )
)
